# plugshield.net
KiCad netlist of a schematic drawn in EAGLE
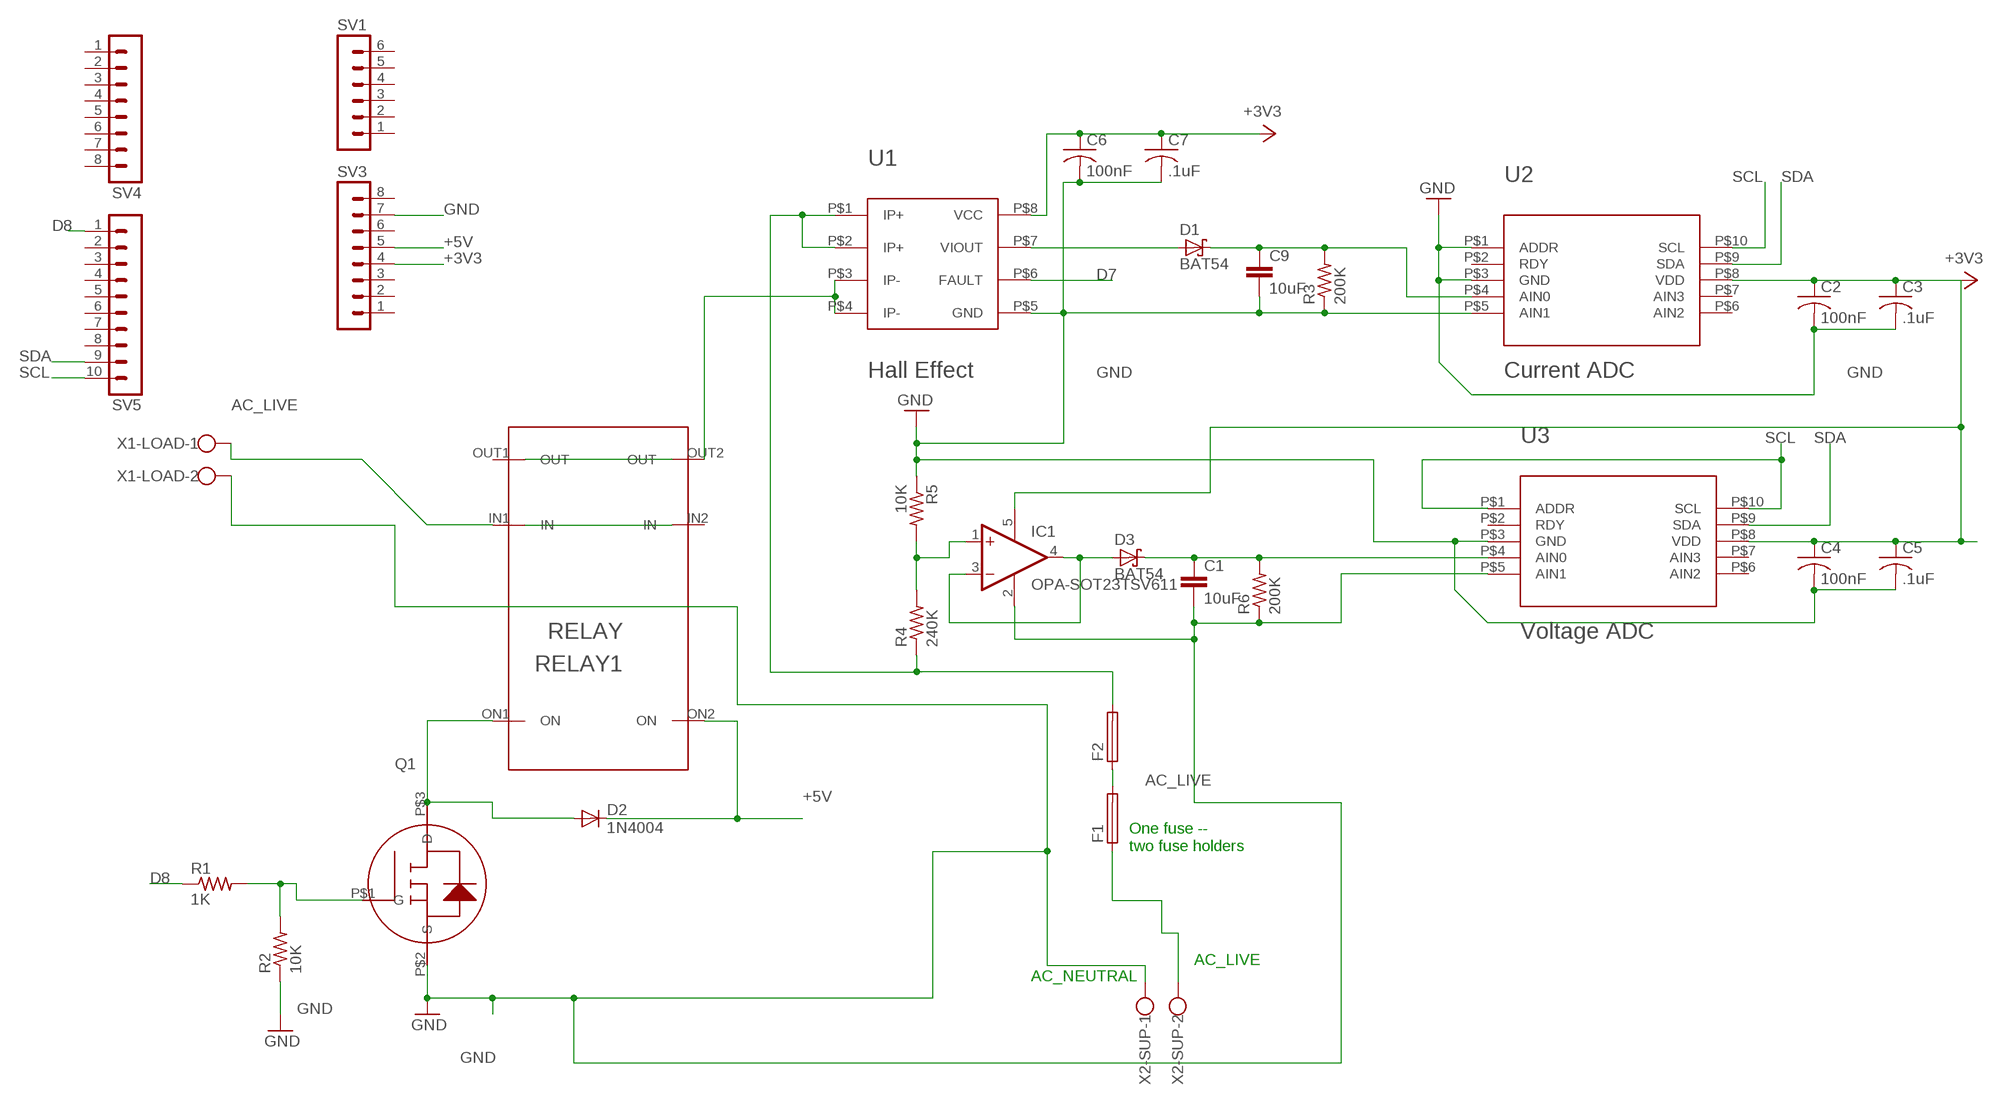
[diagram p0: schematic, sheet 1]

(export (version "E")
  (design (tool "Eeschema 10.0.6"))
  (components
    (comp (ref "C1")
      (value "10uF")
      (footprint "eagle-import:C0805")
      (libsource (lib "eagle-import") (part "C-EUC0805"))
    )
    (comp (ref "C2")
      (value "100nF")
      (footprint "eagle-import:C1206")
      (libsource (lib "eagle-import") (part "C-USC1206"))
    )
    (comp (ref "C3")
      (value ".1uF")
      (footprint "eagle-import:C1206")
      (libsource (lib "eagle-import") (part "C-USC1206"))
    )
    (comp (ref "C4")
      (value "100nF")
      (footprint "eagle-import:C1206")
      (libsource (lib "eagle-import") (part "C-USC1206"))
    )
    (comp (ref "C5")
      (value ".1uF")
      (footprint "eagle-import:C1206")
      (libsource (lib "eagle-import") (part "C-USC1206"))
    )
    (comp (ref "C6")
      (value "100nF")
      (footprint "eagle-import:C1206")
      (libsource (lib "eagle-import") (part "C-USC1206"))
    )
    (comp (ref "C7")
      (value ".1uF")
      (footprint "eagle-import:C1206")
      (libsource (lib "eagle-import") (part "C-USC1206"))
    )
    (comp (ref "C9")
      (value "10uF")
      (footprint "eagle-import:C0805")
      (libsource (lib "eagle-import") (part "C-EUC0805"))
    )
    (comp (ref "D1")
      (value "BAT54")
      (footprint "eagle-import:SOT23")
      (libsource (lib "eagle-import") (part "BAT54"))
    )
    (comp (ref "D2")
      (value "1N4004")
      (footprint "eagle-import:DO41-10")
      (libsource (lib "eagle-import") (part "1N4004"))
    )
    (comp (ref "D3")
      (value "BAT54")
      (footprint "eagle-import:SOT23")
      (libsource (lib "eagle-import") (part "BAT54"))
    )
    (comp (ref "F1")
      (value "19560")
      (footprint "eagle-import:19560")
      (fields (field (name "MPN") "56000001009"))
      (libsource (lib "eagle-import") (part "19560"))
    )
    (comp (ref "F2")
      (value "19560")
      (footprint "eagle-import:19560")
      (fields (field (name "MPN") "56000001009"))
      (libsource (lib "eagle-import") (part "19560"))
    )
    (comp (ref "IC1")
      (value "OPA-SOT23TSV611")
      (footprint "eagle-import:SOT23-5")
      (libsource (lib "eagle-import") (part "OPA-SOT23TSV611"))
    )
    (comp (ref "Q1")
      (value "BSH105")
      (footprint "eagle-import:SOT23")
      (libsource (lib "eagle-import") (part "BSH105"))
    )
    (comp (ref "R1")
      (value "1K")
      (footprint "eagle-import:0411_15")
      (libsource (lib "eagle-import") (part "R-US_CT14J"))
    )
    (comp (ref "R2")
      (value "10K")
      (footprint "eagle-import:0411_15")
      (libsource (lib "eagle-import") (part "R-US_CT14J"))
    )
    (comp (ref "R3")
      (value "200K")
      (footprint "eagle-import:0411_15")
      (libsource (lib "eagle-import") (part "R-US_CT14J"))
    )
    (comp (ref "R4")
      (value "240K")
      (footprint "eagle-import:0411_15")
      (libsource (lib "eagle-import") (part "R-US_0411/15"))
    )
    (comp (ref "R5")
      (value "10K")
      (footprint "eagle-import:0411_15")
      (libsource (lib "eagle-import") (part "R-US_0411/15"))
    )
    (comp (ref "R6")
      (value "200K")
      (footprint "eagle-import:0411_15")
      (libsource (lib "eagle-import") (part "R-US_CT14J"))
    )
    (comp (ref "RELAY1")
      (value "RELAY")
      (footprint "eagle-import:G5RL-1A-E-HR")
      (libsource (lib "eagle-import") (part "G5RL-1A-E-HR"))
    )
    (comp (ref "SV1")
      (value "MA06-1")
      (footprint "eagle-import:MA06-1")
      (libsource (lib "eagle-import") (part "MA06-1"))
    )
    (comp (ref "SV3")
      (value "MA08-1")
      (footprint "eagle-import:MA08-1")
      (libsource (lib "eagle-import") (part "MA08-1"))
    )
    (comp (ref "SV4")
      (value "MA08-1")
      (footprint "eagle-import:MA08-1")
      (libsource (lib "eagle-import") (part "MA08-1"))
    )
    (comp (ref "SV5")
      (value "MA10-1")
      (footprint "eagle-import:MA10-1")
      (libsource (lib "eagle-import") (part "MA10-1"))
    )
    (comp (ref "U1")
      (value "Hall Effect")
      (footprint "eagle-import:ACS711")
      (libsource (lib "eagle-import") (part "ACS711LC"))
    )
    (comp (ref "U2")
      (value "Current ADC")
      (footprint "eagle-import:ADS1013")
      (libsource (lib "eagle-import") (part "ADS1013IDGST"))
    )
    (comp (ref "U3")
      (value "Voltage ADC")
      (footprint "eagle-import:ADS1013")
      (libsource (lib "eagle-import") (part "ADS1013IDGST"))
    )
    (comp (ref "X1-LOAD")
      (value "W237-102")
      (footprint "eagle-import:W237-102")
      (fields (field (name "MPN") "237-102"))
      (libsource (lib "eagle-import") (part "W237-102"))
    )
    (comp (ref "X2-SUP")
      (value "W237-102")
      (footprint "eagle-import:W237-102")
      (fields (field (name "MPN") "237-102"))
      (libsource (lib "eagle-import") (part "W237-102"))
    )
  )
  (nets
    (net (code "1") (name "+3V3") (class "Default")
      (node (ref "C2") (pin "1") (pinfunction "1_1") (pintype "passive"))
      (node (ref "C3") (pin "1") (pinfunction "1_1") (pintype "passive"))
      (node (ref "C4") (pin "1") (pinfunction "1_1") (pintype "passive"))
      (node (ref "C5") (pin "1") (pinfunction "1_1") (pintype "passive"))
      (node (ref "C6") (pin "1") (pinfunction "1_1") (pintype "passive"))
      (node (ref "C7") (pin "1") (pinfunction "1_1") (pintype "passive"))
      (node (ref "IC1") (pin "5") (pinfunction "V+_5") (pintype "power_in"))
      (node (ref "SV3") (pin "4") (pinfunction "4_4") (pintype "passive"))
      (node (ref "U1") (pin "P$8") (pinfunction "VCC_P$8") (pintype "power_in"))
      (node (ref "U2") (pin "P$8") (pinfunction "VDD_P$8") (pintype "power_in"))
      (node (ref "U3") (pin "P$8") (pinfunction "VDD_P$8") (pintype "power_in"))
    )
    (net (code "2") (name "/+5V") (class "Default")
      (node (ref "D2") (pin "C") (pinfunction "C_C") (pintype "passive"))
      (node (ref "RELAY1") (pin "ON2") (pinfunction "ON_ON2") (pintype "bidirectional"))
      (node (ref "SV3") (pin "5") (pinfunction "5_5") (pintype "passive"))
    )
    (net (code "3") (name "/AC_LIVE") (class "Default")
      (node (ref "F1") (pin "1") (pinfunction "1_1") (pintype "passive"))
      (node (ref "F1") (pin "2") (pinfunction "2_2") (pintype "passive"))
      (node (ref "F2") (pin "1") (pinfunction "1_1") (pintype "passive"))
      (node (ref "F2") (pin "2") (pinfunction "2_2") (pintype "passive"))
      (node (ref "R4") (pin "1") (pinfunction "1_1") (pintype "passive"))
      (node (ref "RELAY1") (pin "IN1") (pinfunction "IN_IN1") (pintype "bidirectional"))
      (node (ref "RELAY1") (pin "OUT2") (pinfunction "OUT_OUT2") (pintype "bidirectional"))
      (node (ref "U1") (pin "P$1") (pinfunction "IP+_P$1") (pintype "bidirectional"))
      (node (ref "U1") (pin "P$2") (pinfunction "IP+_P$2") (pintype "bidirectional"))
      (node (ref "U1") (pin "P$3") (pinfunction "IP-_P$3") (pintype "bidirectional"))
      (node (ref "U1") (pin "P$4") (pinfunction "IP-_P$4") (pintype "bidirectional"))
      (node (ref "X1-LOAD") (pin "1") (pinfunction "KL_1") (pintype "passive"))
      (node (ref "X2-SUP") (pin "2") (pinfunction "KL_2") (pintype "passive"))
    )
    (net (code "4") (name "/D7") (class "Default")
      (node (ref "U1") (pin "P$6") (pinfunction "FAULT_P$6") (pintype "bidirectional"))
    )
    (net (code "5") (name "/D8") (class "Default")
      (node (ref "R1") (pin "1") (pinfunction "1_1") (pintype "passive"))
      (node (ref "SV5") (pin "1") (pinfunction "1_1") (pintype "passive"))
    )
    (net (code "6") (name "/SCL") (class "Default")
      (node (ref "SV5") (pin "10") (pinfunction "10_10") (pintype "passive"))
      (node (ref "U2") (pin "P$10") (pinfunction "SCL_P$10") (pintype "bidirectional"))
      (node (ref "U3") (pin "P$1") (pinfunction "ADDR_P$1") (pintype "bidirectional"))
      (node (ref "U3") (pin "P$10") (pinfunction "SCL_P$10") (pintype "bidirectional"))
    )
    (net (code "7") (name "/SDA") (class "Default")
      (node (ref "SV5") (pin "9") (pinfunction "9_9") (pintype "passive"))
      (node (ref "U2") (pin "P$9") (pinfunction "SDA_P$9") (pintype "bidirectional"))
      (node (ref "U3") (pin "P$9") (pinfunction "SDA_P$9") (pintype "bidirectional"))
    )
    (net (code "8") (name "GND") (class "Default")
      (node (ref "C1") (pin "2") (pinfunction "2_2") (pintype "passive"))
      (node (ref "C2") (pin "2") (pinfunction "2_2") (pintype "passive"))
      (node (ref "C3") (pin "2") (pinfunction "2_2") (pintype "passive"))
      (node (ref "C4") (pin "2") (pinfunction "2_2") (pintype "passive"))
      (node (ref "C5") (pin "2") (pinfunction "2_2") (pintype "passive"))
      (node (ref "C6") (pin "2") (pinfunction "2_2") (pintype "passive"))
      (node (ref "C7") (pin "2") (pinfunction "2_2") (pintype "passive"))
      (node (ref "C9") (pin "2") (pinfunction "2_2") (pintype "passive"))
      (node (ref "IC1") (pin "2") (pinfunction "V-_2") (pintype "power_in"))
      (node (ref "Q1") (pin "P$2") (pinfunction "S_P$2") (pintype "input"))
      (node (ref "R2") (pin "1") (pinfunction "1_1") (pintype "passive"))
      (node (ref "R3") (pin "1") (pinfunction "1_1") (pintype "passive"))
      (node (ref "R5") (pin "1") (pinfunction "1_1") (pintype "passive"))
      (node (ref "R6") (pin "1") (pinfunction "1_1") (pintype "passive"))
      (node (ref "SV3") (pin "7") (pinfunction "7_7") (pintype "passive"))
      (node (ref "U1") (pin "P$5") (pinfunction "GND_P$5") (pintype "power_in"))
      (node (ref "U2") (pin "P$1") (pinfunction "ADDR_P$1") (pintype "bidirectional"))
      (node (ref "U2") (pin "P$3") (pinfunction "GND_P$3") (pintype "power_in"))
      (node (ref "U2") (pin "P$5") (pinfunction "AIN1_P$5") (pintype "bidirectional"))
      (node (ref "U3") (pin "P$3") (pinfunction "GND_P$3") (pintype "power_in"))
      (node (ref "U3") (pin "P$5") (pinfunction "AIN1_P$5") (pintype "bidirectional"))
      (node (ref "X1-LOAD") (pin "2") (pinfunction "KL_2") (pintype "passive"))
      (node (ref "X2-SUP") (pin "1") (pinfunction "KL_1") (pintype "passive"))
    )
    (net (code "9") (name "Net-(D1-A)") (class "Default")
      (node (ref "D1") (pin "1") (pinfunction "A_1") (pintype "passive"))
      (node (ref "U1") (pin "P$7") (pinfunction "VIOUT_P$7") (pintype "bidirectional"))
    )
    (net (code "10") (name "Net-(D1-C)") (class "Default")
      (node (ref "C9") (pin "1") (pinfunction "1_1") (pintype "passive"))
      (node (ref "D1") (pin "3") (pinfunction "C_3") (pintype "passive"))
      (node (ref "R3") (pin "2") (pinfunction "2_2") (pintype "passive"))
      (node (ref "U2") (pin "P$4") (pinfunction "AIN0_P$4") (pintype "bidirectional"))
    )
    (net (code "11") (name "Net-(D3-A)") (class "Default")
      (node (ref "D3") (pin "1") (pinfunction "A_1") (pintype "passive"))
      (node (ref "IC1") (pin "3") (pinfunction "-IN_3") (pintype "input"))
      (node (ref "IC1") (pin "4") (pinfunction "OUT_4") (pintype "output"))
    )
    (net (code "12") (name "Net-(D3-C)") (class "Default")
      (node (ref "C1") (pin "1") (pinfunction "1_1") (pintype "passive"))
      (node (ref "D3") (pin "3") (pinfunction "C_3") (pintype "passive"))
      (node (ref "R6") (pin "2") (pinfunction "2_2") (pintype "passive"))
      (node (ref "U3") (pin "P$4") (pinfunction "AIN0_P$4") (pintype "bidirectional"))
    )
    (net (code "13") (name "Net-(IC1-+IN)") (class "Default")
      (node (ref "IC1") (pin "1") (pinfunction "+IN_1") (pintype "input"))
      (node (ref "R4") (pin "2") (pinfunction "2_2") (pintype "passive"))
      (node (ref "R5") (pin "2") (pinfunction "2_2") (pintype "passive"))
    )
    (net (code "14") (name "Net-(Q1-D)") (class "Default")
      (node (ref "D2") (pin "A") (pinfunction "A_A") (pintype "passive"))
      (node (ref "Q1") (pin "P$3") (pinfunction "D_P$3") (pintype "input"))
      (node (ref "RELAY1") (pin "ON1") (pinfunction "ON_ON1") (pintype "bidirectional"))
    )
    (net (code "15") (name "Net-(Q1-G)") (class "Default")
      (node (ref "Q1") (pin "P$1") (pinfunction "G_P$1") (pintype "output"))
      (node (ref "R1") (pin "2") (pinfunction "2_2") (pintype "passive"))
      (node (ref "R2") (pin "2") (pinfunction "2_2") (pintype "passive"))
    )
    (net (code "16") (name "unconnected-(RELAY1-IN-PadIN2)") (class "Default")
      (node (ref "RELAY1") (pin "IN2") (pinfunction "IN_IN2") (pintype "bidirectional"))
    )
    (net (code "17") (name "unconnected-(RELAY1-OUT-PadOUT1)") (class "Default")
      (node (ref "RELAY1") (pin "OUT1") (pinfunction "OUT_OUT1") (pintype "bidirectional"))
    )
    (net (code "18") (name "unconnected-(SV1-Pad1)") (class "Default")
      (node (ref "SV1") (pin "1") (pinfunction "1_1") (pintype "passive"))
    )
    (net (code "19") (name "unconnected-(SV1-Pad2)") (class "Default")
      (node (ref "SV1") (pin "2") (pinfunction "2_2") (pintype "passive"))
    )
    (net (code "20") (name "unconnected-(SV1-Pad3)") (class "Default")
      (node (ref "SV1") (pin "3") (pinfunction "3_3") (pintype "passive"))
    )
    (net (code "21") (name "unconnected-(SV1-Pad4)") (class "Default")
      (node (ref "SV1") (pin "4") (pinfunction "4_4") (pintype "passive"))
    )
    (net (code "22") (name "unconnected-(SV1-Pad5)") (class "Default")
      (node (ref "SV1") (pin "5") (pinfunction "5_5") (pintype "passive"))
    )
    (net (code "23") (name "unconnected-(SV1-Pad6)") (class "Default")
      (node (ref "SV1") (pin "6") (pinfunction "6_6") (pintype "passive"))
    )
    (net (code "24") (name "unconnected-(SV3-Pad1)") (class "Default")
      (node (ref "SV3") (pin "1") (pinfunction "1_1") (pintype "passive"))
    )
    (net (code "25") (name "unconnected-(SV3-Pad2)") (class "Default")
      (node (ref "SV3") (pin "2") (pinfunction "2_2") (pintype "passive"))
    )
    (net (code "26") (name "unconnected-(SV3-Pad3)") (class "Default")
      (node (ref "SV3") (pin "3") (pinfunction "3_3") (pintype "passive"))
    )
    (net (code "27") (name "unconnected-(SV3-Pad6)") (class "Default")
      (node (ref "SV3") (pin "6") (pinfunction "6_6") (pintype "passive"))
    )
    (net (code "28") (name "unconnected-(SV3-Pad8)") (class "Default")
      (node (ref "SV3") (pin "8") (pinfunction "8_8") (pintype "passive"))
    )
    (net (code "29") (name "unconnected-(SV4-Pad1)") (class "Default")
      (node (ref "SV4") (pin "1") (pinfunction "1_1") (pintype "passive"))
    )
    (net (code "30") (name "unconnected-(SV4-Pad2)") (class "Default")
      (node (ref "SV4") (pin "2") (pinfunction "2_2") (pintype "passive"))
    )
    (net (code "31") (name "unconnected-(SV4-Pad3)") (class "Default")
      (node (ref "SV4") (pin "3") (pinfunction "3_3") (pintype "passive"))
    )
    (net (code "32") (name "unconnected-(SV4-Pad4)") (class "Default")
      (node (ref "SV4") (pin "4") (pinfunction "4_4") (pintype "passive"))
    )
    (net (code "33") (name "unconnected-(SV4-Pad5)") (class "Default")
      (node (ref "SV4") (pin "5") (pinfunction "5_5") (pintype "passive"))
    )
    (net (code "34") (name "unconnected-(SV4-Pad6)") (class "Default")
      (node (ref "SV4") (pin "6") (pinfunction "6_6") (pintype "passive"))
    )
    (net (code "35") (name "unconnected-(SV4-Pad7)") (class "Default")
      (node (ref "SV4") (pin "7") (pinfunction "7_7") (pintype "passive"))
    )
    (net (code "36") (name "unconnected-(SV4-Pad8)") (class "Default")
      (node (ref "SV4") (pin "8") (pinfunction "8_8") (pintype "passive"))
    )
    (net (code "37") (name "unconnected-(SV5-Pad2)") (class "Default")
      (node (ref "SV5") (pin "2") (pinfunction "2_2") (pintype "passive"))
    )
    (net (code "38") (name "unconnected-(SV5-Pad3)") (class "Default")
      (node (ref "SV5") (pin "3") (pinfunction "3_3") (pintype "passive"))
    )
    (net (code "39") (name "unconnected-(SV5-Pad4)") (class "Default")
      (node (ref "SV5") (pin "4") (pinfunction "4_4") (pintype "passive"))
    )
    (net (code "40") (name "unconnected-(SV5-Pad5)") (class "Default")
      (node (ref "SV5") (pin "5") (pinfunction "5_5") (pintype "passive"))
    )
    (net (code "41") (name "unconnected-(SV5-Pad6)") (class "Default")
      (node (ref "SV5") (pin "6") (pinfunction "6_6") (pintype "passive"))
    )
    (net (code "42") (name "unconnected-(SV5-Pad7)") (class "Default")
      (node (ref "SV5") (pin "7") (pinfunction "7_7") (pintype "passive"))
    )
    (net (code "43") (name "unconnected-(SV5-Pad8)") (class "Default")
      (node (ref "SV5") (pin "8") (pinfunction "8_8") (pintype "passive"))
    )
    (net (code "44") (name "unconnected-(U2-AIN2-PadP$6)") (class "Default")
      (node (ref "U2") (pin "P$6") (pinfunction "AIN2_P$6") (pintype "no_connect"))
    )
    (net (code "45") (name "unconnected-(U2-AIN3-PadP$7)") (class "Default")
      (node (ref "U2") (pin "P$7") (pinfunction "AIN3_P$7") (pintype "no_connect"))
    )
    (net (code "46") (name "unconnected-(U2-RDY-PadP$2)") (class "Default")
      (node (ref "U2") (pin "P$2") (pinfunction "RDY_P$2") (pintype "no_connect"))
    )
    (net (code "47") (name "unconnected-(U3-AIN2-PadP$6)") (class "Default")
      (node (ref "U3") (pin "P$6") (pinfunction "AIN2_P$6") (pintype "no_connect"))
    )
    (net (code "48") (name "unconnected-(U3-AIN3-PadP$7)") (class "Default")
      (node (ref "U3") (pin "P$7") (pinfunction "AIN3_P$7") (pintype "no_connect"))
    )
    (net (code "49") (name "unconnected-(U3-RDY-PadP$2)") (class "Default")
      (node (ref "U3") (pin "P$2") (pinfunction "RDY_P$2") (pintype "no_connect"))
    )
  )
)
